# CC3D_micro.net
KiCad netlist of a schematic drawn in EAGLE
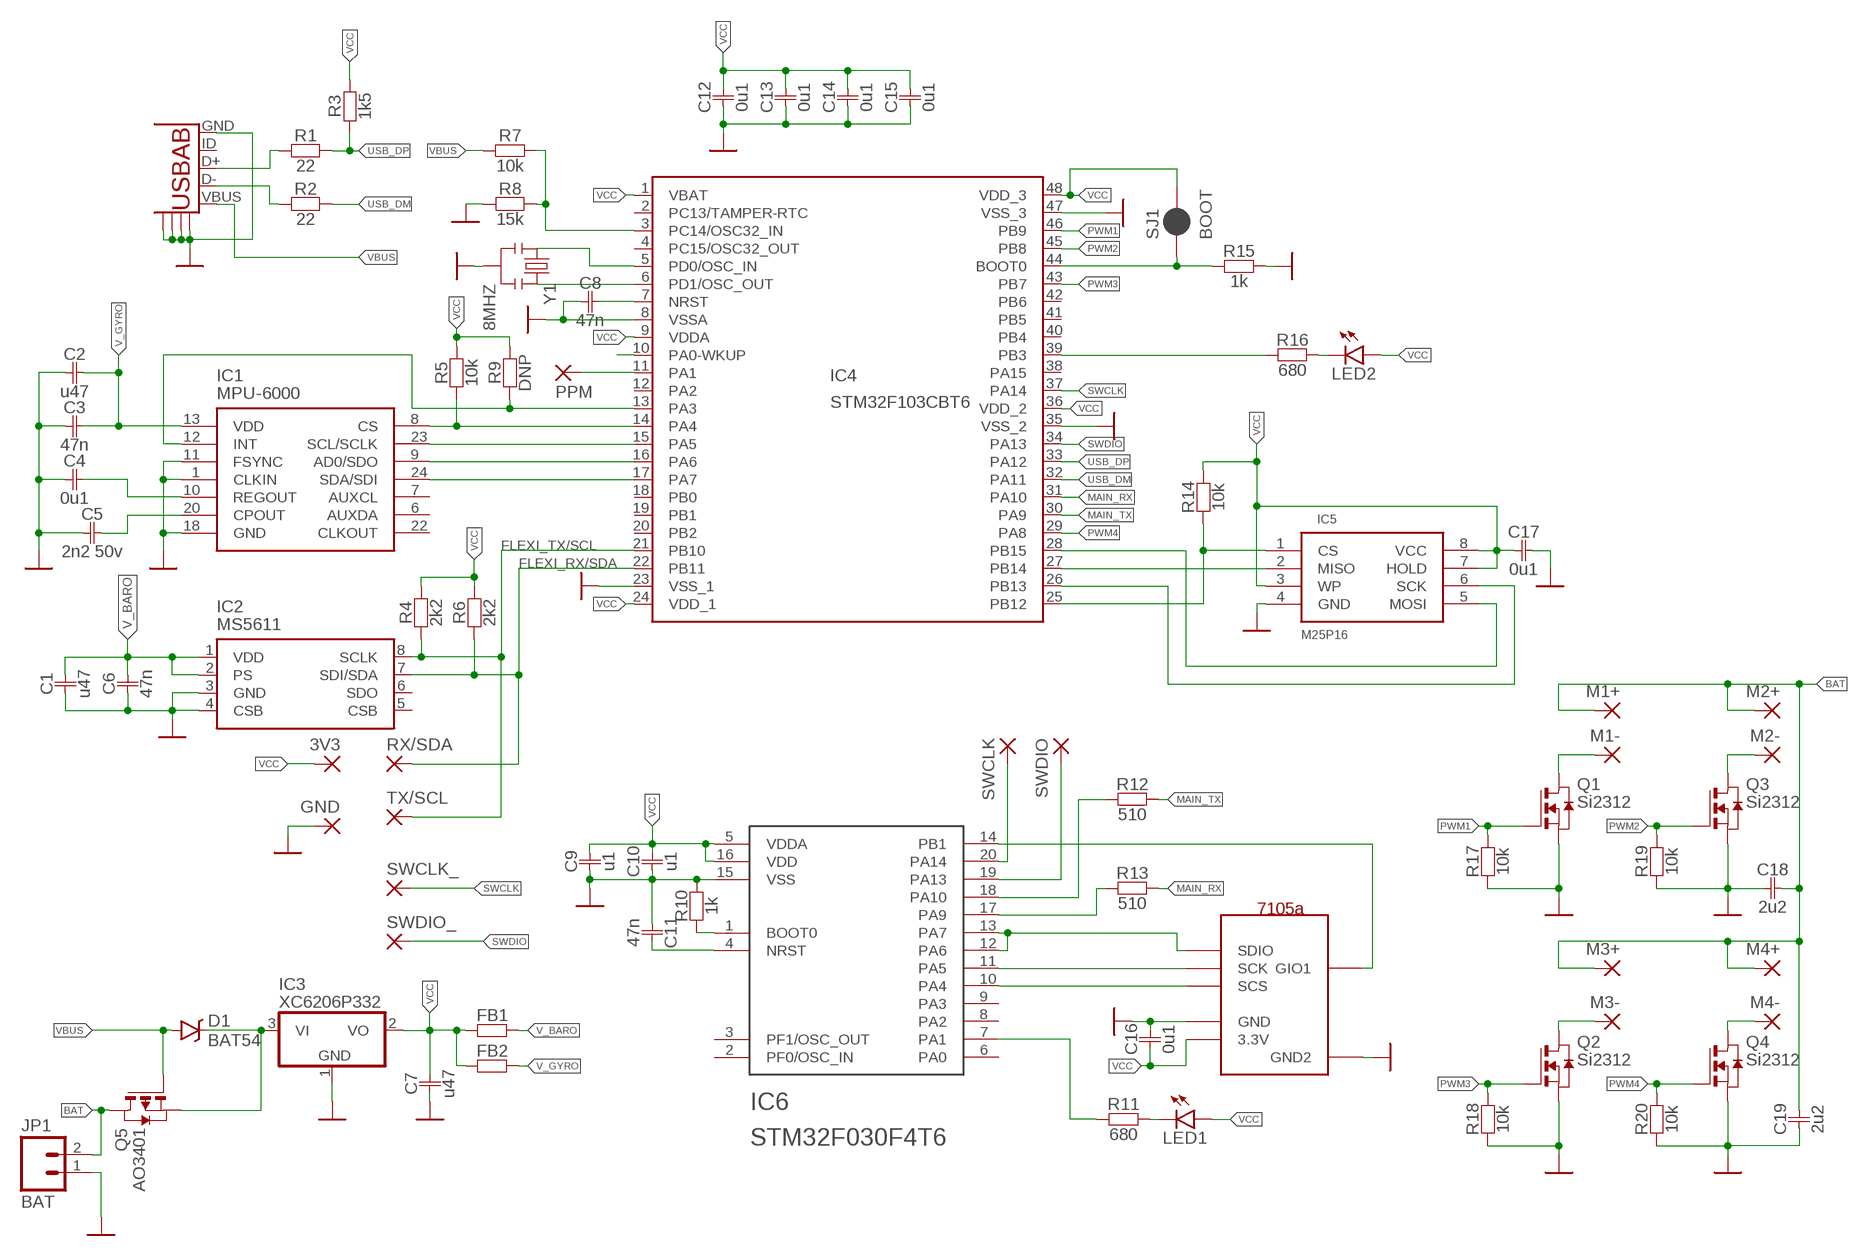
[diagram p0: schematic, sheet 1]

(export (version "E")
  (design (tool "Eeschema 10.0.6"))
  (components
    (comp (ref "3V3")
      (value "SMD2")
      (footprint "eagle-import:SMD1,27-2,54")
      (libsource (lib "eagle-import") (part "SMD2"))
    )
    (comp (ref "C1")
      (value "u47")
      (footprint "eagle-import:0402")
      (libsource (lib "eagle-import") (part "C0402"))
    )
    (comp (ref "C2")
      (value "u47")
      (footprint "eagle-import:0402")
      (libsource (lib "eagle-import") (part "C0402"))
    )
    (comp (ref "C3")
      (value "47n")
      (footprint "eagle-import:0402")
      (libsource (lib "eagle-import") (part "C0402"))
    )
    (comp (ref "C4")
      (value "0u1")
      (footprint "eagle-import:0402")
      (libsource (lib "eagle-import") (part "C0402"))
    )
    (comp (ref "C5")
      (value "2n2 50v")
      (footprint "eagle-import:0402")
      (libsource (lib "eagle-import") (part "C0402"))
    )
    (comp (ref "C6")
      (value "47n")
      (footprint "eagle-import:0402")
      (libsource (lib "eagle-import") (part "C0402"))
    )
    (comp (ref "C7")
      (value "u47")
      (footprint "eagle-import:0805")
      (libsource (lib "eagle-import") (part "C0805"))
    )
    (comp (ref "C8")
      (value "47n")
      (footprint "eagle-import:0402")
      (libsource (lib "eagle-import") (part "C0402"))
    )
    (comp (ref "C9")
      (value "u1")
      (footprint "eagle-import:0402")
      (libsource (lib "eagle-import") (part "C0402"))
    )
    (comp (ref "C10")
      (value "u1")
      (footprint "eagle-import:0402")
      (libsource (lib "eagle-import") (part "C0402"))
    )
    (comp (ref "C11")
      (value "47n")
      (footprint "eagle-import:0402")
      (libsource (lib "eagle-import") (part "C0402"))
    )
    (comp (ref "C12")
      (value "0u1")
      (footprint "eagle-import:0402")
      (libsource (lib "eagle-import") (part "C0402"))
    )
    (comp (ref "C13")
      (value "0u1")
      (footprint "eagle-import:0402")
      (libsource (lib "eagle-import") (part "C0402"))
    )
    (comp (ref "C14")
      (value "0u1")
      (footprint "eagle-import:0402")
      (libsource (lib "eagle-import") (part "C0402"))
    )
    (comp (ref "C15")
      (value "0u1")
      (footprint "eagle-import:0402")
      (libsource (lib "eagle-import") (part "C0402"))
    )
    (comp (ref "C16")
      (value "0u1")
      (footprint "eagle-import:0603")
      (libsource (lib "eagle-import") (part "C0603"))
    )
    (comp (ref "C17")
      (value "0u1")
      (footprint "eagle-import:0402")
      (libsource (lib "eagle-import") (part "C0402"))
    )
    (comp (ref "C18")
      (value "2u2")
      (footprint "eagle-import:0805")
      (libsource (lib "eagle-import") (part "C0805"))
    )
    (comp (ref "C19")
      (value "2u2")
      (footprint "eagle-import:0805")
      (libsource (lib "eagle-import") (part "C0805"))
    )
    (comp (ref "D1")
      (value "BAT54")
      (footprint "eagle-import:SOD-323")
      (libsource (lib "eagle-import") (part "BAT20JFILM"))
    )
    (comp (ref "FB1")
      (value "R0603")
      (footprint "eagle-import:0603")
      (libsource (lib "eagle-import") (part "R0603"))
    )
    (comp (ref "FB2")
      (value "R0603")
      (footprint "eagle-import:0603")
      (libsource (lib "eagle-import") (part "R0603"))
    )
    (comp (ref "GND")
      (value "SMD2")
      (footprint "eagle-import:SMD1,27-2,54")
      (libsource (lib "eagle-import") (part "SMD2"))
    )
    (comp (ref "IC1")
      (value "MPU-6000")
      (footprint "eagle-import:QFN-24-TESTING")
      (libsource (lib "eagle-import") (part "MPU-6050"))
    )
    (comp (ref "IC2")
      (value "MS5611")
      (footprint "eagle-import:LGA8")
      (libsource (lib "eagle-import") (part "MS5611"))
    )
    (comp (ref "IC3")
      (value "XC6206P332")
      (footprint "eagle-import:SOT23")
      (libsource (lib "eagle-import") (part "MCP1703CB"))
    )
    (comp (ref "IC4")
      (value "STM32F103CBT6")
      (footprint "eagle-import:LQFP48")
      (libsource (lib "eagle-import") (part "STM32F103C8"))
    )
    (comp (ref "IC5")
      (value "M25P16")
      (footprint "eagle-import:SO08")
      (libsource (lib "eagle-import") (part "SPI_FLASH-X25XXSMD"))
    )
    (comp (ref "IC6")
      (value "STM32F030F4T6")
      (footprint "eagle-import:TSSOP-20")
      (libsource (lib "eagle-import") (part "STM32F030XTSSOP20"))
    )
    (comp (ref "JP1")
      (value "BAT")
      (footprint "eagle-import:1X02_NO_SILK")
      (libsource (lib "eagle-import") (part "M021X02_NO_SILK"))
    )
    (comp (ref "LED1")
      (value "LED0603")
      (footprint "eagle-import:LED-0603")
      (libsource (lib "eagle-import") (part "LED0603"))
    )
    (comp (ref "LED2")
      (value "LED0603")
      (footprint "eagle-import:LED-0603")
      (libsource (lib "eagle-import") (part "LED0603"))
    )
    (comp (ref "M1+")
      (value "SMD2")
      (footprint "eagle-import:SMD1,27-2,54")
      (libsource (lib "eagle-import") (part "SMD2"))
    )
    (comp (ref "M1-")
      (value "SMD2")
      (footprint "eagle-import:SMD1,27-2,54")
      (libsource (lib "eagle-import") (part "SMD2"))
    )
    (comp (ref "M2+")
      (value "SMD2")
      (footprint "eagle-import:SMD1,27-2,54")
      (libsource (lib "eagle-import") (part "SMD2"))
    )
    (comp (ref "M2-")
      (value "SMD2")
      (footprint "eagle-import:SMD1,27-2,54")
      (libsource (lib "eagle-import") (part "SMD2"))
    )
    (comp (ref "M3+")
      (value "SMD2")
      (footprint "eagle-import:SMD1,27-2,54")
      (libsource (lib "eagle-import") (part "SMD2"))
    )
    (comp (ref "M3-")
      (value "SMD2")
      (footprint "eagle-import:SMD1,27-2,54")
      (libsource (lib "eagle-import") (part "SMD2"))
    )
    (comp (ref "M4+")
      (value "SMD2")
      (footprint "eagle-import:SMD1,27-2,54")
      (libsource (lib "eagle-import") (part "SMD2"))
    )
    (comp (ref "M4-")
      (value "SMD2")
      (footprint "eagle-import:SMD1,27-2,54")
      (libsource (lib "eagle-import") (part "SMD2"))
    )
    (comp (ref "PPM")
      (value "SMD2")
      (footprint "eagle-import:SMD1,27-2,54")
      (libsource (lib "eagle-import") (part "SMD2"))
    )
    (comp (ref "Q1")
      (value "Si2312")
      (footprint "eagle-import:SOT-23")
      (libsource (lib "eagle-import") (part "NMOSSOT23"))
    )
    (comp (ref "Q2")
      (value "Si2312")
      (footprint "eagle-import:SOT-23")
      (libsource (lib "eagle-import") (part "NMOSSOT23"))
    )
    (comp (ref "Q3")
      (value "Si2312")
      (footprint "eagle-import:SOT-23")
      (libsource (lib "eagle-import") (part "NMOSSOT23"))
    )
    (comp (ref "Q4")
      (value "Si2312")
      (footprint "eagle-import:SOT-23")
      (libsource (lib "eagle-import") (part "NMOSSOT23"))
    )
    (comp (ref "Q5")
      (value "AO3401")
      (footprint "eagle-import:SOT-23")
      (libsource (lib "eagle-import") (part "PMOSSOT23"))
    )
    (comp (ref "R1")
      (value "22")
      (footprint "eagle-import:0402")
      (libsource (lib "eagle-import") (part "R0402"))
    )
    (comp (ref "R2")
      (value "22")
      (footprint "eagle-import:0402")
      (libsource (lib "eagle-import") (part "R0402"))
    )
    (comp (ref "R3")
      (value "1k5")
      (footprint "eagle-import:0402")
      (libsource (lib "eagle-import") (part "R0402"))
    )
    (comp (ref "R4")
      (value "2k2")
      (footprint "eagle-import:0402")
      (libsource (lib "eagle-import") (part "R0402"))
    )
    (comp (ref "R5")
      (value "10k")
      (footprint "eagle-import:0402")
      (libsource (lib "eagle-import") (part "R0402"))
    )
    (comp (ref "R6")
      (value "2k2")
      (footprint "eagle-import:0402")
      (libsource (lib "eagle-import") (part "R0402"))
    )
    (comp (ref "R7")
      (value "10k")
      (footprint "eagle-import:0402")
      (libsource (lib "eagle-import") (part "R0402"))
    )
    (comp (ref "R8")
      (value "15k")
      (footprint "eagle-import:0402")
      (libsource (lib "eagle-import") (part "R0402"))
    )
    (comp (ref "R9")
      (value "DNP")
      (footprint "eagle-import:0402")
      (libsource (lib "eagle-import") (part "R0402"))
    )
    (comp (ref "R10")
      (value "1k")
      (footprint "eagle-import:0402")
      (libsource (lib "eagle-import") (part "R0402"))
    )
    (comp (ref "R11")
      (value "680")
      (footprint "eagle-import:0402")
      (libsource (lib "eagle-import") (part "R0402"))
    )
    (comp (ref "R12")
      (value "510")
      (footprint "eagle-import:0402")
      (libsource (lib "eagle-import") (part "R0402"))
    )
    (comp (ref "R13")
      (value "510")
      (footprint "eagle-import:0402")
      (libsource (lib "eagle-import") (part "R0402"))
    )
    (comp (ref "R14")
      (value "10k")
      (footprint "eagle-import:0402")
      (libsource (lib "eagle-import") (part "R0402"))
    )
    (comp (ref "R15")
      (value "1k")
      (footprint "eagle-import:0402")
      (libsource (lib "eagle-import") (part "R0402"))
    )
    (comp (ref "R16")
      (value "680")
      (footprint "eagle-import:0402")
      (libsource (lib "eagle-import") (part "R0402"))
    )
    (comp (ref "R17")
      (value "10k")
      (footprint "eagle-import:0402")
      (libsource (lib "eagle-import") (part "R0402"))
    )
    (comp (ref "R18")
      (value "10k")
      (footprint "eagle-import:0402")
      (libsource (lib "eagle-import") (part "R0402"))
    )
    (comp (ref "R19")
      (value "10k")
      (footprint "eagle-import:0402")
      (libsource (lib "eagle-import") (part "R0402"))
    )
    (comp (ref "R20")
      (value "10k")
      (footprint "eagle-import:0402")
      (libsource (lib "eagle-import") (part "R0402"))
    )
    (comp (ref "RX/SDA")
      (value "SMD2")
      (footprint "eagle-import:SMD1,27-2,54")
      (libsource (lib "eagle-import") (part "SMD2"))
    )
    (comp (ref "SJ1")
      (value "BOOT")
      (footprint "eagle-import:PAD-JUMPER-2-NC_BY_PASTE_YES_SILK")
      (libsource (lib "eagle-import") (part "JUMPER-PAD-2-NC_BY_PASTE"))
    )
    (comp (ref "SWCLK")
      (value "SMD2")
      (footprint "eagle-import:SMD1,27-2,54")
      (libsource (lib "eagle-import") (part "SMD2"))
    )
    (comp (ref "SWCLK_")
      (value "SMD2")
      (footprint "eagle-import:SMD1,27-2,54")
      (libsource (lib "eagle-import") (part "SMD2"))
    )
    (comp (ref "SWDIO")
      (value "SMD2")
      (footprint "eagle-import:SMD1,27-2,54")
      (libsource (lib "eagle-import") (part "SMD2"))
    )
    (comp (ref "SWDIO_")
      (value "SMD2")
      (footprint "eagle-import:SMD1,27-2,54")
      (libsource (lib "eagle-import") (part "SMD2"))
    )
    (comp (ref "TX/SCL")
      (value "SMD2")
      (footprint "eagle-import:SMD1,27-2,54")
      (libsource (lib "eagle-import") (part "SMD2"))
    )
    (comp (ref "U$1")
      (value "microUSB")
      (footprint "eagle-import:UNTITLED_USB-AB-MICRO-SMD")
      (libsource (lib "eagle-import") (part "UNTITLED_USB_AB"))
    )
    (comp (ref "U$2")
      (value "XL7105-SL-B-TH")
      (footprint "eagle-import:XL7105-SY-B")
      (libsource (lib "eagle-import") (part "XL7105-SL-B-TH"))
    )
    (comp (ref "Y1")
      (value "8MHZ")
      (footprint "eagle-import:RESONATOR-SMD")
      (libsource (lib "eagle-import") (part "RESONATOR8MHZ"))
    )
  )
  (nets
    (net (code "1") (name "/FLEXI_RX{slash}SDA") (class "Default")
      (node (ref "IC2") (pin "7") (pinfunction "SDI/SDA_7") (pintype "bidirectional"))
      (node (ref "IC4") (pin "22") (pinfunction "PB11_22") (pintype "bidirectional"))
      (node (ref "R6") (pin "P$1") (pinfunction "P$1_P$1") (pintype "passive"))
      (node (ref "RX/SDA") (pin "1") (pinfunction "P_1") (pintype "passive"))
    )
    (net (code "2") (name "/FLEXI_TX{slash}SCL") (class "Default")
      (node (ref "IC2") (pin "8") (pinfunction "SCLK_8") (pintype "input"))
      (node (ref "IC4") (pin "21") (pinfunction "PB10_21") (pintype "bidirectional"))
      (node (ref "R4") (pin "P$1") (pinfunction "P$1_P$1") (pintype "passive"))
      (node (ref "TX/SCL") (pin "1") (pinfunction "P_1") (pintype "passive"))
    )
    (net (code "3") (name "BAT") (class "Default")
      (node (ref "C18") (pin "P$2") (pinfunction "P$2_P$2") (pintype "passive"))
      (node (ref "C19") (pin "P$2") (pinfunction "P$2_P$2") (pintype "passive"))
      (node (ref "JP1") (pin "2") (pinfunction "2_2") (pintype "passive"))
      (node (ref "M1+") (pin "1") (pinfunction "P_1") (pintype "passive"))
      (node (ref "M2+") (pin "1") (pinfunction "P_1") (pintype "passive"))
      (node (ref "M3+") (pin "1") (pinfunction "P_1") (pintype "passive"))
      (node (ref "M4+") (pin "1") (pinfunction "P_1") (pintype "passive"))
      (node (ref "Q5") (pin "1") (pinfunction "D_1") (pintype "passive"))
    )
    (net (code "4") (name "GND") (class "Default")
      (node (ref "C1") (pin "P$1") (pinfunction "P$1_P$1") (pintype "passive"))
      (node (ref "C10") (pin "P$2") (pinfunction "P$2_P$2") (pintype "passive"))
      (node (ref "C11") (pin "P$1") (pinfunction "P$1_P$1") (pintype "passive"))
      (node (ref "C12") (pin "P$1") (pinfunction "P$1_P$1") (pintype "passive"))
      (node (ref "C13") (pin "P$1") (pinfunction "P$1_P$1") (pintype "passive"))
      (node (ref "C14") (pin "P$1") (pinfunction "P$1_P$1") (pintype "passive"))
      (node (ref "C15") (pin "P$1") (pinfunction "P$1_P$1") (pintype "passive"))
      (node (ref "C16") (pin "P$2") (pinfunction "P$2_P$2") (pintype "passive"))
      (node (ref "C17") (pin "P$2") (pinfunction "P$2_P$2") (pintype "passive"))
      (node (ref "C18") (pin "P$1") (pinfunction "P$1_P$1") (pintype "passive"))
      (node (ref "C19") (pin "P$1") (pinfunction "P$1_P$1") (pintype "passive"))
      (node (ref "C2") (pin "P$1") (pinfunction "P$1_P$1") (pintype "passive"))
      (node (ref "C3") (pin "P$1") (pinfunction "P$1_P$1") (pintype "passive"))
      (node (ref "C4") (pin "P$1") (pinfunction "P$1_P$1") (pintype "passive"))
      (node (ref "C5") (pin "P$1") (pinfunction "P$1_P$1") (pintype "passive"))
      (node (ref "C6") (pin "P$1") (pinfunction "P$1_P$1") (pintype "passive"))
      (node (ref "C7") (pin "P$1") (pinfunction "P$1_P$1") (pintype "passive"))
      (node (ref "C8") (pin "P$1") (pinfunction "P$1_P$1") (pintype "passive"))
      (node (ref "C9") (pin "P$1") (pinfunction "P$1_P$1") (pintype "passive"))
      (node (ref "GND") (pin "1") (pinfunction "P_1") (pintype "passive"))
      (node (ref "IC1") (pin "1") (pinfunction "CLKIN_1") (pintype "bidirectional"))
      (node (ref "IC1") (pin "11") (pinfunction "FSYNC_11") (pintype "bidirectional"))
      (node (ref "IC1") (pin "18") (pinfunction "GND_18") (pintype "bidirectional"))
      (node (ref "IC2") (pin "3") (pinfunction "GND_3") (pintype "power_in"))
      (node (ref "IC2") (pin "4") (pinfunction "CSB_4") (pintype "input"))
      (node (ref "IC3") (pin "1") (pinfunction "GND_1") (pintype "passive"))
      (node (ref "IC4") (pin "23") (pinfunction "VSS_1_23") (pintype "power_in"))
      (node (ref "IC4") (pin "35") (pinfunction "VSS_2_35") (pintype "power_in"))
      (node (ref "IC4") (pin "47") (pinfunction "VSS_3_47") (pintype "power_in"))
      (node (ref "IC4") (pin "8") (pinfunction "VSSA_8") (pintype "power_in"))
      (node (ref "IC5") (pin "4") (pinfunction "GND_4") (pintype "bidirectional"))
      (node (ref "IC6") (pin "15") (pinfunction "VSS_15") (pintype "bidirectional"))
      (node (ref "JP1") (pin "1") (pinfunction "1_1") (pintype "passive"))
      (node (ref "Q1") (pin "2") (pinfunction "S_2") (pintype "passive"))
      (node (ref "Q2") (pin "2") (pinfunction "S_2") (pintype "passive"))
      (node (ref "Q3") (pin "2") (pinfunction "S_2") (pintype "passive"))
      (node (ref "Q4") (pin "2") (pinfunction "S_2") (pintype "passive"))
      (node (ref "R10") (pin "P$2") (pinfunction "P$2_P$2") (pintype "passive"))
      (node (ref "R15") (pin "P$2") (pinfunction "P$2_P$2") (pintype "passive"))
      (node (ref "R17") (pin "P$1") (pinfunction "P$1_P$1") (pintype "passive"))
      (node (ref "R18") (pin "P$1") (pinfunction "P$1_P$1") (pintype "passive"))
      (node (ref "R19") (pin "P$1") (pinfunction "P$1_P$1") (pintype "passive"))
      (node (ref "R20") (pin "P$1") (pinfunction "P$1_P$1") (pintype "passive"))
      (node (ref "R8") (pin "P$2") (pinfunction "P$2_P$2") (pintype "passive"))
      (node (ref "U$1") (pin "GND") (pinfunction "GND_GND") (pintype "power_in"))
      (node (ref "U$1") (pin "GND@1") (pinfunction "P$1_GND@1") (pintype "power_in"))
      (node (ref "U$1") (pin "GND@2") (pinfunction "P$2_GND@2") (pintype "power_in"))
      (node (ref "U$1") (pin "GND@3") (pinfunction "P$3_GND@3") (pintype "power_in"))
      (node (ref "U$1") (pin "GND@4") (pinfunction "P$4_GND@4") (pintype "power_in"))
      (node (ref "U$2") (pin "P$2") (pinfunction "GND_P$2") (pintype "bidirectional"))
      (node (ref "U$2") (pin "P$6") (pinfunction "GND2_P$6") (pintype "bidirectional"))
      (node (ref "Y1") (pin "2") (pinfunction "2_2") (pintype "passive"))
    )
    (net (code "5") (name "MAIN_RX") (class "Default")
      (node (ref "IC4") (pin "31") (pinfunction "PA10_31") (pintype "bidirectional"))
      (node (ref "R13") (pin "P$2") (pinfunction "P$2_P$2") (pintype "passive"))
    )
    (net (code "6") (name "MAIN_TX") (class "Default")
      (node (ref "IC4") (pin "30") (pinfunction "PA9_30") (pintype "bidirectional"))
      (node (ref "R12") (pin "P$2") (pinfunction "P$2_P$2") (pintype "passive"))
    )
    (net (code "7") (name "Net-(IC1-AD0{slash}SDO)") (class "Default")
      (node (ref "IC1") (pin "9") (pinfunction "AD0/SDO_9") (pintype "bidirectional"))
      (node (ref "IC4") (pin "16") (pinfunction "PA6_16") (pintype "bidirectional"))
    )
    (net (code "8") (name "Net-(IC1-CPOUT)") (class "Default")
      (node (ref "C5") (pin "P$2") (pinfunction "P$2_P$2") (pintype "passive"))
      (node (ref "IC1") (pin "20") (pinfunction "CPOUT_20") (pintype "bidirectional"))
    )
    (net (code "9") (name "Net-(IC1-CS)") (class "Default")
      (node (ref "IC1") (pin "8") (pinfunction "CS_8") (pintype "bidirectional"))
      (node (ref "IC4") (pin "14") (pinfunction "PA4_14") (pintype "bidirectional"))
      (node (ref "R5") (pin "P$1") (pinfunction "P$1_P$1") (pintype "passive"))
    )
    (net (code "10") (name "Net-(IC1-INT)") (class "Default")
      (node (ref "IC1") (pin "12") (pinfunction "INT_12") (pintype "bidirectional"))
      (node (ref "IC4") (pin "13") (pinfunction "PA3_13") (pintype "bidirectional"))
      (node (ref "R9") (pin "P$1") (pinfunction "P$1_P$1") (pintype "passive"))
    )
    (net (code "11") (name "Net-(IC1-REGOUT)") (class "Default")
      (node (ref "C4") (pin "P$2") (pinfunction "P$2_P$2") (pintype "passive"))
      (node (ref "IC1") (pin "10") (pinfunction "REGOUT_10") (pintype "bidirectional"))
    )
    (net (code "12") (name "Net-(IC1-SCL{slash}SCLK)") (class "Default")
      (node (ref "IC1") (pin "23") (pinfunction "SCL/SCLK_23") (pintype "bidirectional"))
      (node (ref "IC4") (pin "15") (pinfunction "PA5_15") (pintype "bidirectional"))
    )
    (net (code "13") (name "Net-(IC1-SDA{slash}SDI)") (class "Default")
      (node (ref "IC1") (pin "24") (pinfunction "SDA/SDI_24") (pintype "bidirectional"))
      (node (ref "IC4") (pin "17") (pinfunction "PA7_17") (pintype "bidirectional"))
    )
    (net (code "14") (name "Net-(IC3-VI)") (class "Default")
      (node (ref "D1") (pin "C") (pinfunction "C_C") (pintype "passive"))
      (node (ref "IC3") (pin "3") (pinfunction "VI_3") (pintype "input"))
      (node (ref "Q5") (pin "2") (pinfunction "S_2") (pintype "passive"))
    )
    (net (code "15") (name "Net-(IC4-BOOT0)") (class "Default")
      (node (ref "IC4") (pin "44") (pinfunction "BOOT0_44") (pintype "input"))
      (node (ref "R15") (pin "P$1") (pinfunction "P$1_P$1") (pintype "passive"))
      (node (ref "SJ1") (pin "1") (pinfunction "1_1") (pintype "passive"))
    )
    (net (code "16") (name "Net-(IC4-NRST)") (class "Default")
      (node (ref "C8") (pin "P$2") (pinfunction "P$2_P$2") (pintype "passive"))
      (node (ref "IC4") (pin "7") (pinfunction "NRST_7") (pintype "input"))
    )
    (net (code "17") (name "Net-(IC4-PA1)") (class "Default")
      (node (ref "IC4") (pin "11") (pinfunction "PA1_11") (pintype "bidirectional"))
      (node (ref "PPM") (pin "1") (pinfunction "P_1") (pintype "passive"))
    )
    (net (code "18") (name "Net-(IC4-PB3)") (class "Default")
      (node (ref "IC4") (pin "39") (pinfunction "PB3_39") (pintype "bidirectional"))
      (node (ref "R16") (pin "P$1") (pinfunction "P$1_P$1") (pintype "passive"))
    )
    (net (code "19") (name "Net-(IC4-PB12)") (class "Default")
      (node (ref "IC4") (pin "25") (pinfunction "PB12_25") (pintype "bidirectional"))
      (node (ref "IC5") (pin "1") (pinfunction "CS_1") (pintype "bidirectional"))
      (node (ref "R14") (pin "P$1") (pinfunction "P$1_P$1") (pintype "passive"))
    )
    (net (code "20") (name "Net-(IC4-PB13)") (class "Default")
      (node (ref "IC4") (pin "26") (pinfunction "PB13_26") (pintype "bidirectional"))
      (node (ref "IC5") (pin "6") (pinfunction "SCK_6") (pintype "bidirectional"))
    )
    (net (code "21") (name "Net-(IC4-PB14)") (class "Default")
      (node (ref "IC4") (pin "27") (pinfunction "PB14_27") (pintype "bidirectional"))
      (node (ref "IC5") (pin "2") (pinfunction "MISO_2") (pintype "bidirectional"))
    )
    (net (code "22") (name "Net-(IC4-PB15)") (class "Default")
      (node (ref "IC4") (pin "28") (pinfunction "PB15_28") (pintype "bidirectional"))
      (node (ref "IC5") (pin "5") (pinfunction "MOSI_5") (pintype "bidirectional"))
    )
    (net (code "23") (name "Net-(IC4-PC14{slash}OSC32_IN)") (class "Default")
      (node (ref "IC4") (pin "3") (pinfunction "PC14/OSC32_IN_3") (pintype "bidirectional"))
      (node (ref "R7") (pin "P$2") (pinfunction "P$2_P$2") (pintype "passive"))
      (node (ref "R8") (pin "P$1") (pinfunction "P$1_P$1") (pintype "passive"))
    )
    (net (code "24") (name "Net-(IC4-PD0{slash}OSC_IN)") (class "Default")
      (node (ref "IC4") (pin "5") (pinfunction "PD0/OSC_IN_5") (pintype "bidirectional"))
      (node (ref "Y1") (pin "1") (pinfunction "1_1") (pintype "passive"))
    )
    (net (code "25") (name "Net-(IC4-PD1{slash}OSC_OUT)") (class "Default")
      (node (ref "IC4") (pin "6") (pinfunction "PD1/OSC_OUT_6") (pintype "bidirectional"))
      (node (ref "Y1") (pin "3") (pinfunction "3_3") (pintype "passive"))
    )
    (net (code "26") (name "Net-(IC6-BOOT0)") (class "Default")
      (node (ref "IC6") (pin "1") (pinfunction "BOOT0_1") (pintype "bidirectional"))
      (node (ref "R10") (pin "P$1") (pinfunction "P$1_P$1") (pintype "passive"))
    )
    (net (code "27") (name "Net-(IC6-NRST)") (class "Default")
      (node (ref "C11") (pin "P$2") (pinfunction "P$2_P$2") (pintype "passive"))
      (node (ref "IC6") (pin "4") (pinfunction "NRST_4") (pintype "bidirectional"))
    )
    (net (code "28") (name "Net-(IC6-PA1)") (class "Default")
      (node (ref "IC6") (pin "7") (pinfunction "PA1_7") (pintype "bidirectional"))
      (node (ref "R11") (pin "P$1") (pinfunction "P$1_P$1") (pintype "passive"))
    )
    (net (code "29") (name "Net-(IC6-PA4)") (class "Default")
      (node (ref "IC6") (pin "10") (pinfunction "PA4_10") (pintype "bidirectional"))
      (node (ref "U$2") (pin "P$3") (pinfunction "SCS_P$3") (pintype "bidirectional"))
    )
    (net (code "30") (name "Net-(IC6-PA5)") (class "Default")
      (node (ref "IC6") (pin "11") (pinfunction "PA5_11") (pintype "bidirectional"))
      (node (ref "U$2") (pin "P$4") (pinfunction "SCK_P$4") (pintype "bidirectional"))
    )
    (net (code "31") (name "Net-(IC6-PA6)") (class "Default")
      (node (ref "IC6") (pin "12") (pinfunction "PA6_12") (pintype "bidirectional"))
      (node (ref "IC6") (pin "13") (pinfunction "PA7_13") (pintype "bidirectional"))
      (node (ref "U$2") (pin "P$5") (pinfunction "SDIO_P$5") (pintype "bidirectional"))
    )
    (net (code "32") (name "Net-(IC6-PA9)") (class "Default")
      (node (ref "IC6") (pin "17") (pinfunction "PA9_17") (pintype "bidirectional"))
      (node (ref "R13") (pin "P$1") (pinfunction "P$1_P$1") (pintype "passive"))
    )
    (net (code "33") (name "Net-(IC6-PA10)") (class "Default")
      (node (ref "IC6") (pin "18") (pinfunction "PA10_18") (pintype "bidirectional"))
      (node (ref "R12") (pin "P$1") (pinfunction "P$1_P$1") (pintype "passive"))
    )
    (net (code "34") (name "Net-(IC6-PA13)") (class "Default")
      (node (ref "IC6") (pin "19") (pinfunction "PA13_19") (pintype "bidirectional"))
      (node (ref "SWDIO") (pin "1") (pinfunction "P_1") (pintype "passive"))
    )
    (net (code "35") (name "Net-(IC6-PA14)") (class "Default")
      (node (ref "IC6") (pin "20") (pinfunction "PA14_20") (pintype "bidirectional"))
      (node (ref "SWCLK") (pin "1") (pinfunction "P_1") (pintype "passive"))
    )
    (net (code "36") (name "Net-(IC6-PB1)") (class "Default")
      (node (ref "IC6") (pin "14") (pinfunction "PB1_14") (pintype "bidirectional"))
      (node (ref "U$2") (pin "P$7") (pinfunction "GIO1_P$7") (pintype "bidirectional"))
    )
    (net (code "37") (name "Net-(LED1-PadC)") (class "Default")
      (node (ref "LED1") (pin "C") (pinfunction "C_C") (pintype "passive"))
      (node (ref "R11") (pin "P$2") (pinfunction "P$2_P$2") (pintype "passive"))
    )
    (net (code "38") (name "Net-(LED2-PadC)") (class "Default")
      (node (ref "LED2") (pin "C") (pinfunction "C_C") (pintype "passive"))
      (node (ref "R16") (pin "P$2") (pinfunction "P$2_P$2") (pintype "passive"))
    )
    (net (code "39") (name "Net-(M1--P)") (class "Default")
      (node (ref "M1-") (pin "1") (pinfunction "P_1") (pintype "passive"))
      (node (ref "Q1") (pin "1") (pinfunction "D_1") (pintype "passive"))
    )
    (net (code "40") (name "Net-(M2--P)") (class "Default")
      (node (ref "M2-") (pin "1") (pinfunction "P_1") (pintype "passive"))
      (node (ref "Q3") (pin "1") (pinfunction "D_1") (pintype "passive"))
    )
    (net (code "41") (name "Net-(M3--P)") (class "Default")
      (node (ref "M3-") (pin "1") (pinfunction "P_1") (pintype "passive"))
      (node (ref "Q2") (pin "1") (pinfunction "D_1") (pintype "passive"))
    )
    (net (code "42") (name "Net-(M4--P)") (class "Default")
      (node (ref "M4-") (pin "1") (pinfunction "P_1") (pintype "passive"))
      (node (ref "Q4") (pin "1") (pinfunction "D_1") (pintype "passive"))
    )
    (net (code "43") (name "Net-(R1-PadP$2)") (class "Default")
      (node (ref "R1") (pin "P$2") (pinfunction "P$2_P$2") (pintype "passive"))
      (node (ref "U$1") (pin "D+") (pinfunction "D+_D+") (pintype "bidirectional"))
    )
    (net (code "44") (name "Net-(R2-PadP$2)") (class "Default")
      (node (ref "R2") (pin "P$2") (pinfunction "P$2_P$2") (pintype "passive"))
      (node (ref "U$1") (pin "D-") (pinfunction "D-_D-") (pintype "bidirectional"))
    )
    (net (code "45") (name "PWM1") (class "Default")
      (node (ref "IC4") (pin "46") (pinfunction "PB9_46") (pintype "bidirectional"))
      (node (ref "Q1") (pin "3") (pinfunction "G_3") (pintype "passive"))
      (node (ref "R17") (pin "P$2") (pinfunction "P$2_P$2") (pintype "passive"))
    )
    (net (code "46") (name "PWM2") (class "Default")
      (node (ref "IC4") (pin "45") (pinfunction "PB8_45") (pintype "bidirectional"))
      (node (ref "Q3") (pin "3") (pinfunction "G_3") (pintype "passive"))
      (node (ref "R19") (pin "P$2") (pinfunction "P$2_P$2") (pintype "passive"))
    )
    (net (code "47") (name "PWM3") (class "Default")
      (node (ref "IC4") (pin "43") (pinfunction "PB7_43") (pintype "bidirectional"))
      (node (ref "Q2") (pin "3") (pinfunction "G_3") (pintype "passive"))
      (node (ref "R18") (pin "P$2") (pinfunction "P$2_P$2") (pintype "passive"))
    )
    (net (code "48") (name "PWM4") (class "Default")
      (node (ref "IC4") (pin "29") (pinfunction "PA8_29") (pintype "bidirectional"))
      (node (ref "Q4") (pin "3") (pinfunction "G_3") (pintype "passive"))
      (node (ref "R20") (pin "P$2") (pinfunction "P$2_P$2") (pintype "passive"))
    )
    (net (code "49") (name "SWCLK") (class "Default")
      (node (ref "IC4") (pin "37") (pinfunction "PA14_37") (pintype "bidirectional"))
      (node (ref "SWCLK_") (pin "1") (pinfunction "P_1") (pintype "passive"))
    )
    (net (code "50") (name "SWDIO") (class "Default")
      (node (ref "IC4") (pin "34") (pinfunction "PA13_34") (pintype "bidirectional"))
      (node (ref "SWDIO_") (pin "1") (pinfunction "P_1") (pintype "passive"))
    )
    (net (code "51") (name "USB_DM") (class "Default")
      (node (ref "IC4") (pin "32") (pinfunction "PA11_32") (pintype "bidirectional"))
      (node (ref "R2") (pin "P$1") (pinfunction "P$1_P$1") (pintype "passive"))
    )
    (net (code "52") (name "USB_DP") (class "Default")
      (node (ref "IC4") (pin "33") (pinfunction "PA12_33") (pintype "bidirectional"))
      (node (ref "R1") (pin "P$1") (pinfunction "P$1_P$1") (pintype "passive"))
      (node (ref "R3") (pin "P$2") (pinfunction "P$2_P$2") (pintype "passive"))
    )
    (net (code "53") (name "VBUS") (class "Default")
      (node (ref "D1") (pin "A") (pinfunction "A_A") (pintype "passive"))
      (node (ref "Q5") (pin "3") (pinfunction "G_3") (pintype "passive"))
      (node (ref "R7") (pin "P$1") (pinfunction "P$1_P$1") (pintype "passive"))
      (node (ref "U$1") (pin "VBUS") (pinfunction "VBUS_VBUS") (pintype "power_in"))
    )
    (net (code "54") (name "VCC") (class "Default")
      (node (ref "3V3") (pin "1") (pinfunction "P_1") (pintype "passive"))
      (node (ref "C10") (pin "P$1") (pinfunction "P$1_P$1") (pintype "passive"))
      (node (ref "C12") (pin "P$2") (pinfunction "P$2_P$2") (pintype "passive"))
      (node (ref "C13") (pin "P$2") (pinfunction "P$2_P$2") (pintype "passive"))
      (node (ref "C14") (pin "P$2") (pinfunction "P$2_P$2") (pintype "passive"))
      (node (ref "C15") (pin "P$2") (pinfunction "P$2_P$2") (pintype "passive"))
      (node (ref "C16") (pin "P$1") (pinfunction "P$1_P$1") (pintype "passive"))
      (node (ref "C17") (pin "P$1") (pinfunction "P$1_P$1") (pintype "passive"))
      (node (ref "C7") (pin "P$2") (pinfunction "P$2_P$2") (pintype "passive"))
      (node (ref "C9") (pin "P$2") (pinfunction "P$2_P$2") (pintype "passive"))
      (node (ref "FB1") (pin "P$1") (pinfunction "P$1_P$1") (pintype "passive"))
      (node (ref "FB2") (pin "P$1") (pinfunction "P$1_P$1") (pintype "passive"))
      (node (ref "IC3") (pin "2") (pinfunction "VO_2") (pintype "passive"))
      (node (ref "IC4") (pin "1") (pinfunction "VBAT_1") (pintype "power_in"))
      (node (ref "IC4") (pin "24") (pinfunction "VDD_1_24") (pintype "power_in"))
      (node (ref "IC4") (pin "36") (pinfunction "VDD_2_36") (pintype "power_in"))
      (node (ref "IC4") (pin "48") (pinfunction "VDD_3_48") (pintype "power_in"))
      (node (ref "IC4") (pin "9") (pinfunction "VDDA_9") (pintype "power_in"))
      (node (ref "IC5") (pin "3") (pinfunction "WP_3") (pintype "bidirectional"))
      (node (ref "IC5") (pin "7") (pinfunction "HOLD_7") (pintype "bidirectional"))
      (node (ref "IC5") (pin "8") (pinfunction "VCC_8") (pintype "bidirectional"))
      (node (ref "IC6") (pin "16") (pinfunction "VDD_16") (pintype "bidirectional"))
      (node (ref "IC6") (pin "5") (pinfunction "VDDA_5") (pintype "bidirectional"))
      (node (ref "LED1") (pin "A") (pinfunction "A_A") (pintype "passive"))
      (node (ref "LED2") (pin "A") (pinfunction "A_A") (pintype "passive"))
      (node (ref "R14") (pin "P$2") (pinfunction "P$2_P$2") (pintype "passive"))
      (node (ref "R3") (pin "P$1") (pinfunction "P$1_P$1") (pintype "passive"))
      (node (ref "R4") (pin "P$2") (pinfunction "P$2_P$2") (pintype "passive"))
      (node (ref "R5") (pin "P$2") (pinfunction "P$2_P$2") (pintype "passive"))
      (node (ref "R6") (pin "P$2") (pinfunction "P$2_P$2") (pintype "passive"))
      (node (ref "R9") (pin "P$2") (pinfunction "P$2_P$2") (pintype "passive"))
      (node (ref "SJ1") (pin "2") (pinfunction "2_2") (pintype "passive"))
      (node (ref "U$2") (pin "P$1") (pinfunction "3.3V_P$1") (pintype "bidirectional"))
    )
    (net (code "55") (name "V_BARO") (class "Default")
      (node (ref "C1") (pin "P$2") (pinfunction "P$2_P$2") (pintype "passive"))
      (node (ref "C6") (pin "P$2") (pinfunction "P$2_P$2") (pintype "passive"))
      (node (ref "FB1") (pin "P$2") (pinfunction "P$2_P$2") (pintype "passive"))
      (node (ref "IC2") (pin "1") (pinfunction "VDD_1") (pintype "power_in"))
      (node (ref "IC2") (pin "2") (pinfunction "PS_2") (pintype "input"))
    )
    (net (code "56") (name "V_GYRO") (class "Default")
      (node (ref "C2") (pin "P$2") (pinfunction "P$2_P$2") (pintype "passive"))
      (node (ref "C3") (pin "P$2") (pinfunction "P$2_P$2") (pintype "passive"))
      (node (ref "FB2") (pin "P$2") (pinfunction "P$2_P$2") (pintype "passive"))
      (node (ref "IC1") (pin "13") (pinfunction "VDD_13") (pintype "bidirectional"))
    )
    (net (code "57") (name "unconnected-(IC1-AUXCL-Pad7)") (class "Default")
      (node (ref "IC1") (pin "7") (pinfunction "AUXCL_7") (pintype "bidirectional"))
    )
    (net (code "58") (name "unconnected-(IC1-AUXDA-Pad6)") (class "Default")
      (node (ref "IC1") (pin "6") (pinfunction "AUXDA_6") (pintype "bidirectional"))
    )
    (net (code "59") (name "unconnected-(IC1-CLKOUT-Pad22)") (class "Default")
      (node (ref "IC1") (pin "22") (pinfunction "CLKOUT_22") (pintype "bidirectional"))
    )
    (net (code "60") (name "unconnected-(IC2-CSB-Pad5)") (class "Default")
      (node (ref "IC2") (pin "5") (pinfunction "CSB_5") (pintype "input"))
    )
    (net (code "61") (name "unconnected-(IC2-SDO-Pad6)") (class "Default")
      (node (ref "IC2") (pin "6") (pinfunction "SDO_6") (pintype "output"))
    )
    (net (code "62") (name "unconnected-(IC4-PA0-WKUP-Pad10)") (class "Default")
      (node (ref "IC4") (pin "10") (pinfunction "PA0-WKUP_10") (pintype "bidirectional"))
    )
    (net (code "63") (name "unconnected-(IC4-PA2-Pad12)") (class "Default")
      (node (ref "IC4") (pin "12") (pinfunction "PA2_12") (pintype "bidirectional"))
    )
    (net (code "64") (name "unconnected-(IC4-PA15-Pad38)") (class "Default")
      (node (ref "IC4") (pin "38") (pinfunction "PA15_38") (pintype "bidirectional"))
    )
    (net (code "65") (name "unconnected-(IC4-PB0-Pad18)") (class "Default")
      (node (ref "IC4") (pin "18") (pinfunction "PB0_18") (pintype "bidirectional"))
    )
    (net (code "66") (name "unconnected-(IC4-PB1-Pad19)") (class "Default")
      (node (ref "IC4") (pin "19") (pinfunction "PB1_19") (pintype "bidirectional"))
    )
    (net (code "67") (name "unconnected-(IC4-PB2-Pad20)") (class "Default")
      (node (ref "IC4") (pin "20") (pinfunction "PB2_20") (pintype "bidirectional"))
    )
    (net (code "68") (name "unconnected-(IC4-PB4-Pad40)") (class "Default")
      (node (ref "IC4") (pin "40") (pinfunction "PB4_40") (pintype "bidirectional"))
    )
    (net (code "69") (name "unconnected-(IC4-PB5-Pad41)") (class "Default")
      (node (ref "IC4") (pin "41") (pinfunction "PB5_41") (pintype "bidirectional"))
    )
    (net (code "70") (name "unconnected-(IC4-PB6-Pad42)") (class "Default")
      (node (ref "IC4") (pin "42") (pinfunction "PB6_42") (pintype "bidirectional"))
    )
    (net (code "71") (name "unconnected-(IC4-PC13{slash}TAMPER-RTC-Pad2)") (class "Default")
      (node (ref "IC4") (pin "2") (pinfunction "PC13/TAMPER-RTC_2") (pintype "bidirectional"))
    )
    (net (code "72") (name "unconnected-(IC4-PC15{slash}OSC32_OUT-Pad4)") (class "Default")
      (node (ref "IC4") (pin "4") (pinfunction "PC15/OSC32_OUT_4") (pintype "bidirectional"))
    )
    (net (code "73") (name "unconnected-(IC6-PA0-Pad6)") (class "Default")
      (node (ref "IC6") (pin "6") (pinfunction "PA0_6") (pintype "bidirectional"))
    )
    (net (code "74") (name "unconnected-(IC6-PA2-Pad8)") (class "Default")
      (node (ref "IC6") (pin "8") (pinfunction "PA2_8") (pintype "bidirectional"))
    )
    (net (code "75") (name "unconnected-(IC6-PA3-Pad9)") (class "Default")
      (node (ref "IC6") (pin "9") (pinfunction "PA3_9") (pintype "bidirectional"))
    )
    (net (code "76") (name "unconnected-(IC6-PF0{slash}OSC_IN-Pad2)") (class "Default")
      (node (ref "IC6") (pin "2") (pinfunction "PF0/OSC_IN_2") (pintype "bidirectional"))
    )
    (net (code "77") (name "unconnected-(IC6-PF1{slash}OSC_OUT-Pad3)") (class "Default")
      (node (ref "IC6") (pin "3") (pinfunction "PF1/OSC_OUT_3") (pintype "bidirectional"))
    )
    (net (code "78") (name "unconnected-(U$1-USBID-PadID)") (class "Default")
      (node (ref "U$1") (pin "ID") (pinfunction "USBID_ID") (pintype "bidirectional"))
    )
  )
)
